# TEC_driver.net
KiCad netlist of a schematic drawn in Altium Designer
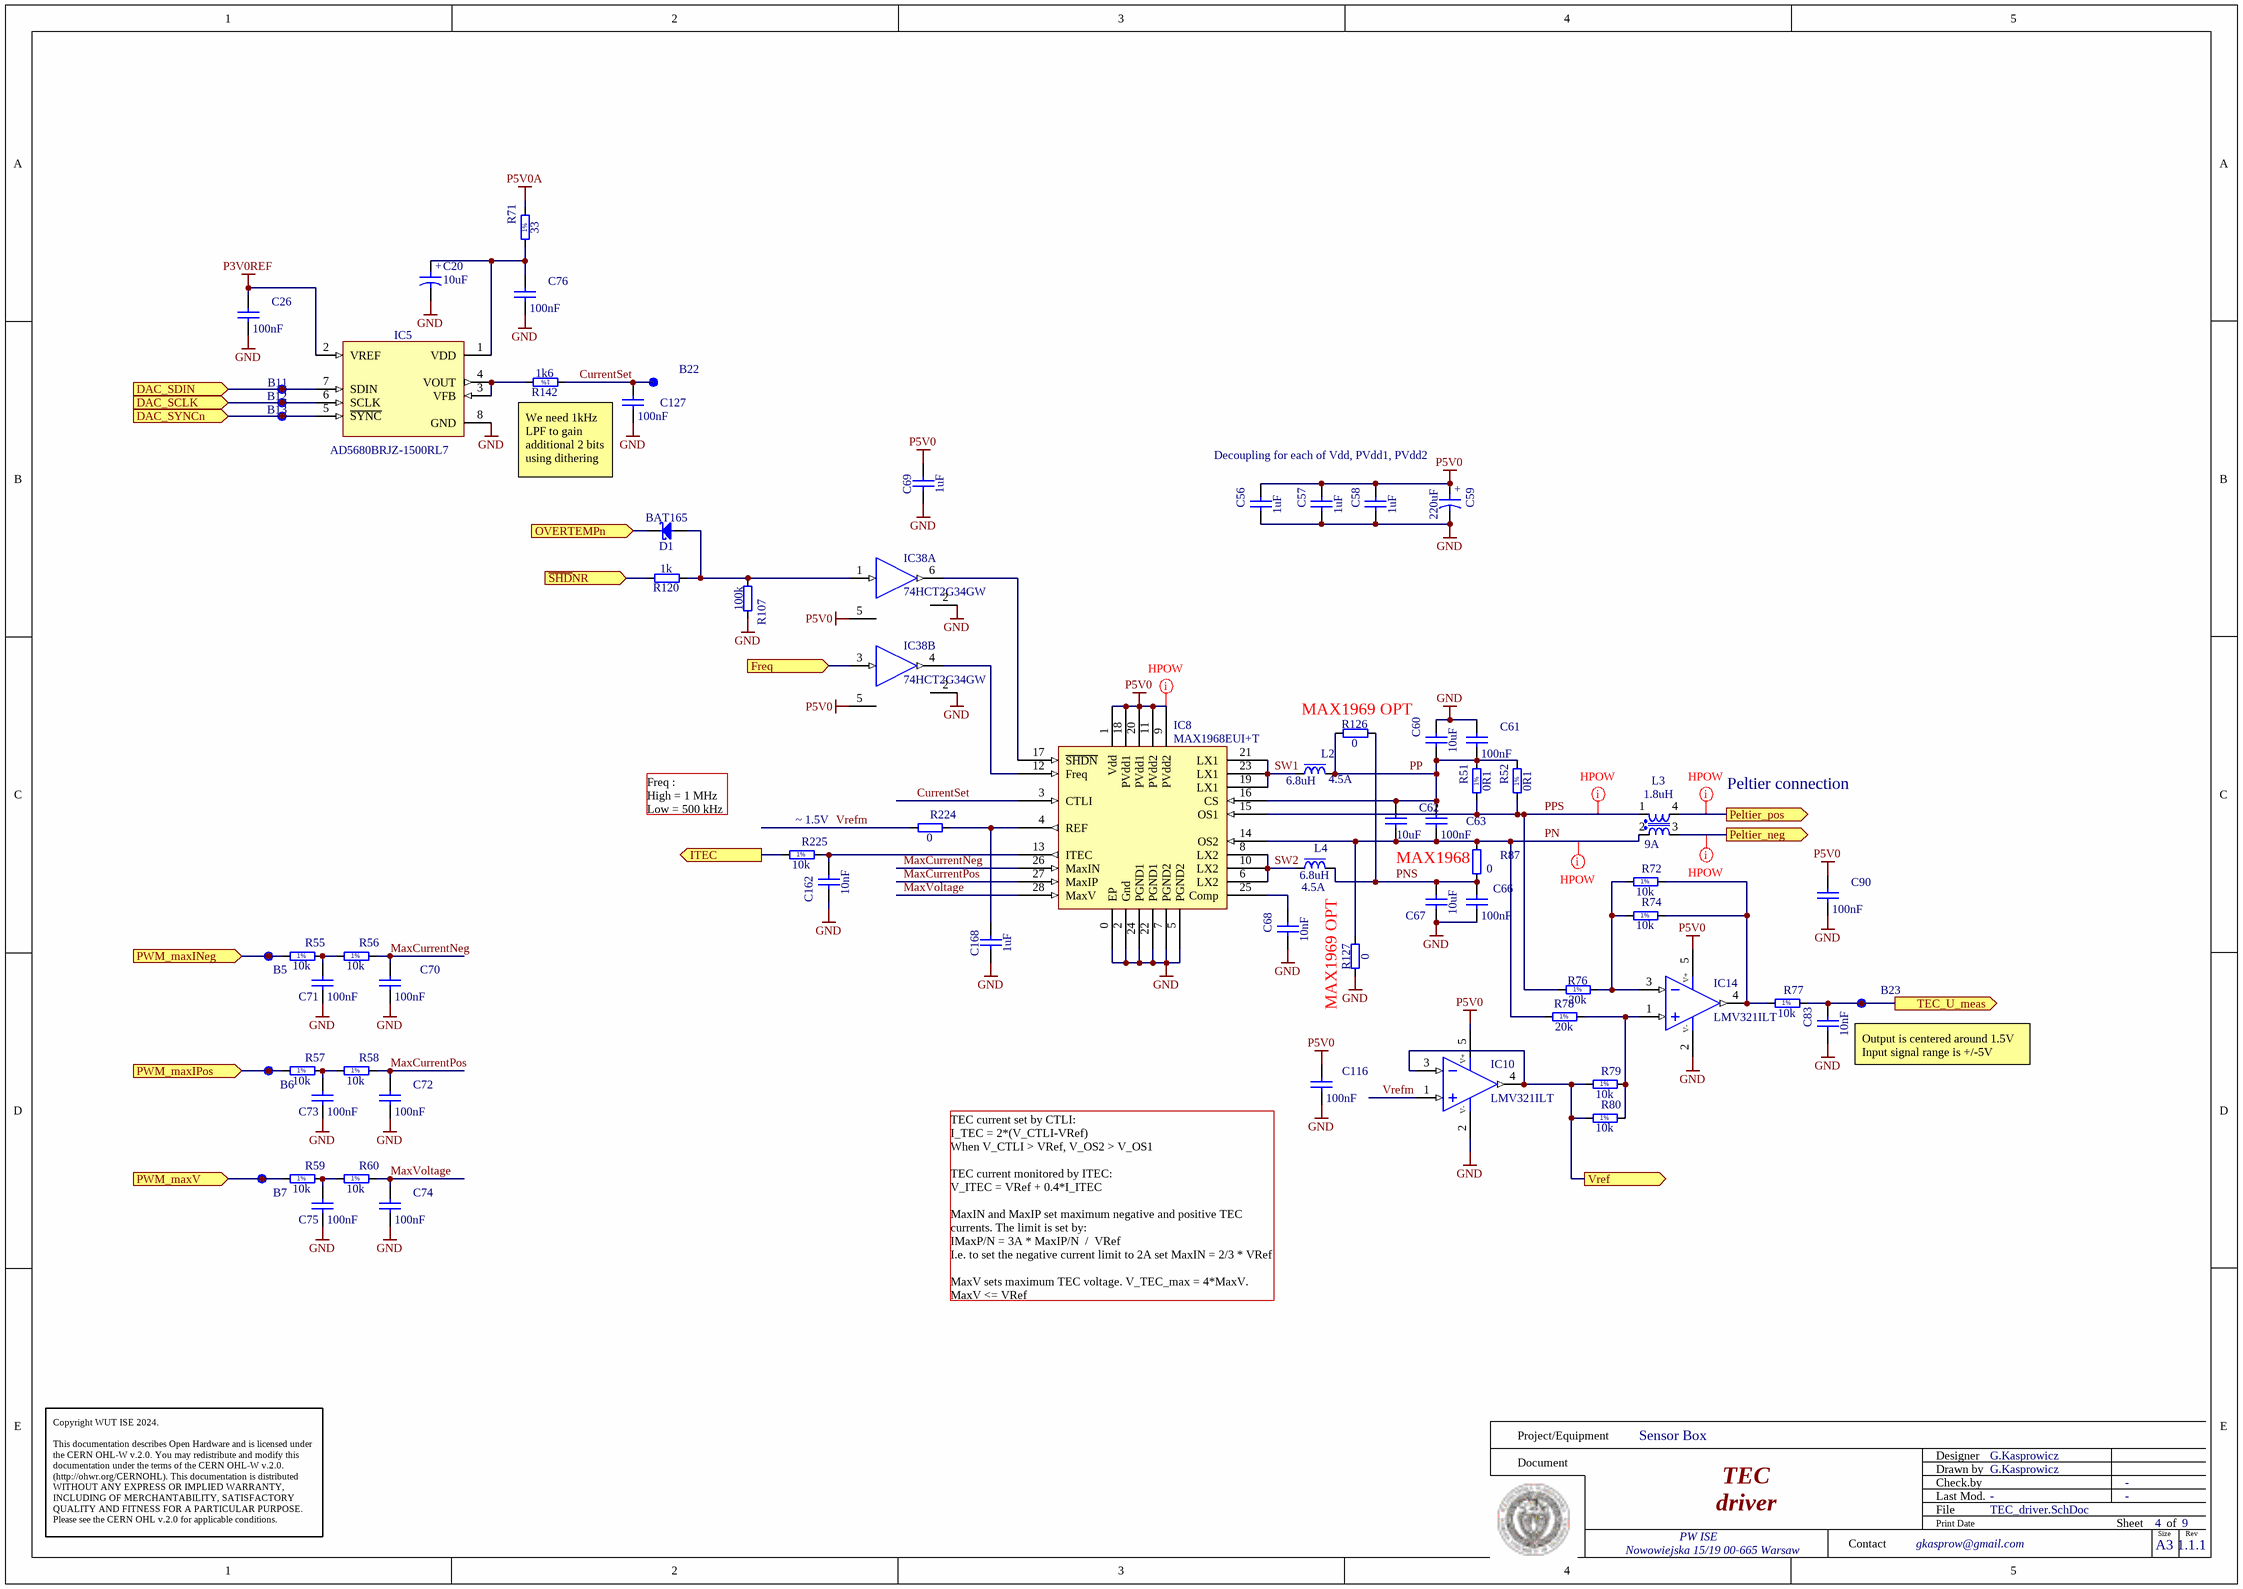
[diagram p0: TEC_driver.SchDoc]

(export (version "E")
  (design (tool "Eeschema 10.0.6"))
  (components
    (comp (ref "B5")
      (value "SMD Pad")
      (footprint "C100")
      (description "Through Hole Pad")
      (fields (field (name "PART NUMBER") "SMD_PAD_D1MM") (field (name "AUTHOR") "CERN DEM JLC"))
      (libsource (lib "Eletro-mechanical") (part "Single SMD Pad (Round)"))
    )
    (comp (ref "B6")
      (value "SMD Pad")
      (footprint "C100")
      (description "Through Hole Pad")
      (fields (field (name "PART NUMBER") "SMD_PAD_D1MM") (field (name "AUTHOR") "CERN DEM JLC"))
      (libsource (lib "Eletro-mechanical") (part "Single SMD Pad (Round)"))
    )
    (comp (ref "B7")
      (value "SMD Pad")
      (footprint "C100")
      (description "Through Hole Pad")
      (fields (field (name "PART NUMBER") "SMD_PAD_D1MM") (field (name "AUTHOR") "CERN DEM JLC"))
      (libsource (lib "Eletro-mechanical") (part "Single SMD Pad (Round)"))
    )
    (comp (ref "B11")
      (value "SMD Pad")
      (footprint "C100")
      (description "Through Hole Pad")
      (fields (field (name "PART NUMBER") "SMD_PAD_D1MM") (field (name "AUTHOR") "CERN DEM JLC"))
      (libsource (lib "Eletro-mechanical") (part "Single SMD Pad (Round)"))
    )
    (comp (ref "B12")
      (value "SMD Pad")
      (footprint "C100")
      (description "Through Hole Pad")
      (fields (field (name "PART NUMBER") "SMD_PAD_D1MM") (field (name "AUTHOR") "CERN DEM JLC"))
      (libsource (lib "Eletro-mechanical") (part "Single SMD Pad (Round)"))
    )
    (comp (ref "B13")
      (value "SMD Pad")
      (footprint "C100")
      (description "Through Hole Pad")
      (fields (field (name "PART NUMBER") "SMD_PAD_D1MM") (field (name "AUTHOR") "CERN DEM JLC"))
      (libsource (lib "Eletro-mechanical") (part "Single SMD Pad (Round)"))
    )
    (comp (ref "B22")
      (value "SMD Pad")
      (footprint "C100")
      (description "Through Hole Pad")
      (fields (field (name "PART NUMBER") "SMD_PAD_D1MM") (field (name "AUTHOR") "CERN DEM JLC"))
      (libsource (lib "Eletro-mechanical") (part "Single SMD Pad (Round)"))
    )
    (comp (ref "B23")
      (value "SMD Pad")
      (footprint "C100")
      (description "Through Hole Pad")
      (fields (field (name "PART NUMBER") "SMD_PAD_D1MM") (field (name "AUTHOR") "CERN DEM JLC"))
      (libsource (lib "Eletro-mechanical") (part "Single SMD Pad (Round)"))
    )
    (comp (ref "C20")
      (value "10uF")
      (footprint "CAPMP3216X180N")
      (description "Polarised capacitor")
      (fields
        (field (name "PART NUMBER") "CTE3216-18_10UF_16V_20%_AVX_TCJ")
        (field (name "VOLTAGE") "16V")
        (field (name "AUTHOR") "CERN DEM JLC")
      )
      (libsource (lib "Capacitors") (part "Capacitor - polarized"))
    )
    (comp (ref "C26")
      (value "100nF")
      (footprint "CAPC1005X55N")
      (description "Non-polarised capacitor")
      (fields
        (field (name "PART NUMBER") "CC0402_100NF_16V_10%_X5R")
        (field (name "VOLTAGE") "16V")
        (field (name "AUTHOR") "CERN DEM JLC")
      )
      (libsource (lib "Capacitors") (part "Capacitor - non polarized"))
    )
    (comp (ref "C56")
      (value "1uF")
      (footprint "CAPC1608X87N")
      (description "Non-polarised capacitor")
      (fields
        (field (name "PART NUMBER") "CC0603_1UF_25V_10%_X7R")
        (field (name "VOLTAGE") "25V")
        (field (name "AUTHOR") "CERN DEM JLC")
      )
      (libsource (lib "Capacitors") (part "Capacitor - non polarized"))
    )
    (comp (ref "C57")
      (value "1uF")
      (footprint "CAPC1608X87N")
      (description "Non-polarised capacitor")
      (fields
        (field (name "PART NUMBER") "CC0603_1UF_25V_10%_X7R")
        (field (name "VOLTAGE") "25V")
        (field (name "AUTHOR") "CERN DEM JLC")
      )
      (libsource (lib "Capacitors") (part "Capacitor - non polarized"))
    )
    (comp (ref "C58")
      (value "1uF")
      (footprint "CAPC1608X87N")
      (description "Non-polarised capacitor")
      (fields
        (field (name "PART NUMBER") "CC0603_1UF_25V_10%_X7R")
        (field (name "VOLTAGE") "25V")
        (field (name "AUTHOR") "CERN DEM JLC")
      )
      (libsource (lib "Capacitors") (part "Capacitor - non polarized"))
    )
    (comp (ref "C59")
      (value "220uF")
      (footprint "CAPMP7343X430N")
      (description "Polarised capacitor")
      (fields
        (field (name "PART NUMBER") "CTE7343-43_220UF_16V_10%")
        (field (name "VOLTAGE") "16V")
        (field (name "AUTHOR") "CERN DEM JLC")
      )
      (libsource (lib "Capacitors") (part "Capacitor - polarized"))
    )
    (comp (ref "C60")
      (value "10uF")
      (footprint "CAPC2012X135N")
      (description "Non-polarised capacitor")
      (fields
        (field (name "PART NUMBER") "CC0805_10UF_16V_10%_X5R")
        (field (name "VOLTAGE") "16V")
        (field (name "AUTHOR") "CERN DEM JLC")
      )
      (libsource (lib "Capacitors") (part "Capacitor - non polarized"))
    )
    (comp (ref "C61")
      (value "100nF")
      (footprint "CAPC1005X55N")
      (description "Non-polarised capacitor")
      (fields
        (field (name "PART NUMBER") "CC0402_100NF_16V_10%_X5R")
        (field (name "VOLTAGE") "16V")
        (field (name "AUTHOR") "CERN DEM JLC")
      )
      (libsource (lib "Capacitors") (part "Capacitor - non polarized"))
    )
    (comp (ref "C62")
      (value "10uF")
      (footprint "CAPC2012X135N")
      (description "Non-polarised capacitor")
      (fields
        (field (name "PART NUMBER") "CC0805_10UF_16V_10%_X5R")
        (field (name "VOLTAGE") "16V")
        (field (name "AUTHOR") "CERN DEM JLC")
      )
      (libsource (lib "Capacitors") (part "Capacitor - non polarized"))
    )
    (comp (ref "C63")
      (value "100nF")
      (footprint "CAPC1005X55N")
      (description "Non-polarised capacitor")
      (fields
        (field (name "PART NUMBER") "CC0402_100NF_16V_10%_X5R")
        (field (name "VOLTAGE") "16V")
        (field (name "AUTHOR") "CERN DEM JLC")
      )
      (libsource (lib "Capacitors") (part "Capacitor - non polarized"))
    )
    (comp (ref "C66")
      (value "100nF")
      (footprint "CAPC1005X55N")
      (description "Non-polarised capacitor")
      (fields
        (field (name "PART NUMBER") "CC0402_100NF_16V_10%_X5R")
        (field (name "VOLTAGE") "16V")
        (field (name "AUTHOR") "CERN DEM JLC")
      )
      (libsource (lib "Capacitors") (part "Capacitor - non polarized"))
    )
    (comp (ref "C67")
      (value "10uF")
      (footprint "CAPC2012X135N")
      (description "Non-polarised capacitor")
      (fields
        (field (name "PART NUMBER") "CC0805_10UF_16V_10%_X5R")
        (field (name "VOLTAGE") "16V")
        (field (name "AUTHOR") "CERN DEM JLC")
      )
      (libsource (lib "Capacitors") (part "Capacitor - non polarized"))
    )
    (comp (ref "C68")
      (value "10nF")
      (footprint "CAPC1005X55N")
      (description "Non-polarised capacitor")
      (fields
        (field (name "PART NUMBER") "CC0402_10NF_25V_10%_X7R")
        (field (name "VOLTAGE") "25V")
        (field (name "AUTHOR") "CERN DEM JLC")
      )
      (libsource (lib "Capacitors") (part "Capacitor - non polarized"))
    )
    (comp (ref "C69")
      (value "1uF")
      (footprint "CAPC1608X87N")
      (description "Non-polarised capacitor")
      (fields
        (field (name "PART NUMBER") "CC0603_1UF_25V_10%_X7R")
        (field (name "VOLTAGE") "25V")
        (field (name "AUTHOR") "CERN DEM JLC")
      )
      (libsource (lib "Capacitors") (part "Capacitor - non polarized"))
    )
    (comp (ref "C70")
      (value "100nF")
      (footprint "CAPC1005X55N")
      (description "Non-polarised capacitor")
      (fields
        (field (name "PART NUMBER") "CC0402_100NF_16V_10%_X5R")
        (field (name "VOLTAGE") "16V")
        (field (name "AUTHOR") "CERN DEM JLC")
      )
      (libsource (lib "Capacitors") (part "Capacitor - non polarized"))
    )
    (comp (ref "C71")
      (value "100nF")
      (footprint "CAPC1005X55N")
      (description "Non-polarised capacitor")
      (fields
        (field (name "PART NUMBER") "CC0402_100NF_16V_10%_X5R")
        (field (name "VOLTAGE") "16V")
        (field (name "AUTHOR") "CERN DEM JLC")
      )
      (libsource (lib "Capacitors") (part "Capacitor - non polarized"))
    )
    (comp (ref "C72")
      (value "100nF")
      (footprint "CAPC1005X55N")
      (description "Non-polarised capacitor")
      (fields
        (field (name "PART NUMBER") "CC0402_100NF_16V_10%_X5R")
        (field (name "VOLTAGE") "16V")
        (field (name "AUTHOR") "CERN DEM JLC")
      )
      (libsource (lib "Capacitors") (part "Capacitor - non polarized"))
    )
    (comp (ref "C73")
      (value "100nF")
      (footprint "CAPC1005X55N")
      (description "Non-polarised capacitor")
      (fields
        (field (name "PART NUMBER") "CC0402_100NF_16V_10%_X5R")
        (field (name "VOLTAGE") "16V")
        (field (name "AUTHOR") "CERN DEM JLC")
      )
      (libsource (lib "Capacitors") (part "Capacitor - non polarized"))
    )
    (comp (ref "C74")
      (value "100nF")
      (footprint "CAPC1005X55N")
      (description "Non-polarised capacitor")
      (fields
        (field (name "PART NUMBER") "CC0402_100NF_16V_10%_X5R")
        (field (name "VOLTAGE") "16V")
        (field (name "AUTHOR") "CERN DEM JLC")
      )
      (libsource (lib "Capacitors") (part "Capacitor - non polarized"))
    )
    (comp (ref "C75")
      (value "100nF")
      (footprint "CAPC1005X55N")
      (description "Non-polarised capacitor")
      (fields
        (field (name "PART NUMBER") "CC0402_100NF_16V_10%_X5R")
        (field (name "VOLTAGE") "16V")
        (field (name "AUTHOR") "CERN DEM JLC")
      )
      (libsource (lib "Capacitors") (part "Capacitor - non polarized"))
    )
    (comp (ref "C76")
      (value "100nF")
      (footprint "CAPC1005X55N")
      (description "Non-polarised capacitor")
      (fields
        (field (name "PART NUMBER") "CC0402_100NF_16V_10%_X5R")
        (field (name "VOLTAGE") "16V")
        (field (name "AUTHOR") "CERN DEM JLC")
      )
      (libsource (lib "Capacitors") (part "Capacitor - non polarized"))
    )
    (comp (ref "C83")
      (value "10nF")
      (footprint "CAPC1005X55N")
      (description "Non-polarised capacitor")
      (fields
        (field (name "PART NUMBER") "CC0402_10NF_25V_10%_X7R")
        (field (name "VOLTAGE") "25V")
        (field (name "AUTHOR") "CERN DEM JLC")
      )
      (libsource (lib "Capacitors") (part "Capacitor - non polarized"))
    )
    (comp (ref "C90")
      (value "100nF")
      (footprint "CAPC1005X55N")
      (description "Non-polarised capacitor")
      (fields
        (field (name "PART NUMBER") "CC0402_100NF_16V_10%_X5R")
        (field (name "VOLTAGE") "16V")
        (field (name "AUTHOR") "CERN DEM JLC")
      )
      (libsource (lib "Capacitors") (part "Capacitor - non polarized"))
    )
    (comp (ref "C116")
      (value "100nF")
      (footprint "CAPC1005X55N")
      (description "Non-polarised capacitor")
      (fields
        (field (name "PART NUMBER") "CC0402_100NF_16V_10%_X5R")
        (field (name "VOLTAGE") "16V")
        (field (name "AUTHOR") "CERN DEM JLC")
      )
      (libsource (lib "Capacitors") (part "Capacitor - non polarized"))
    )
    (comp (ref "C127")
      (value "100nF")
      (footprint "CAPC1005X55N")
      (description "Non-polarised capacitor")
      (fields
        (field (name "PART NUMBER") "CC0402_100NF_16V_10%_X5R")
        (field (name "VOLTAGE") "16V")
        (field (name "AUTHOR") "CERN DEM JLC")
      )
      (libsource (lib "Capacitors") (part "Capacitor - non polarized"))
    )
    (comp (ref "C162")
      (value "10nF")
      (footprint "CAPC1005X55N")
      (description "Non-polarised capacitor")
      (fields
        (field (name "PART NUMBER") "CC0402_10NF_25V_10%_X7R")
        (field (name "VOLTAGE") "25V")
        (field (name "AUTHOR") "CERN DEM JLC")
      )
      (libsource (lib "Capacitors") (part "Capacitor - non polarized"))
    )
    (comp (ref "C168")
      (value "1uF")
      (footprint "CAPC1608X87N")
      (description "Non-polarised capacitor")
      (fields
        (field (name "PART NUMBER") "CC0603_1UF_25V_10%_X7R")
        (field (name "VOLTAGE") "25V")
        (field (name "AUTHOR") "CERN DEM JLC")
      )
      (libsource (lib "Capacitors") (part "Capacitor - non polarized"))
    )
    (comp (ref "D1")
      (value "BAT165")
      (footprint "SOD2512X110N")
      (description "Schottky Diode")
      (fields
        (field (name "VOLTAGE") "40V")
        (field (name "POWER") "750mA")
        (field (name "AUTHOR") "CERN DEM JLC")
      )
      (libsource (lib "ICs And Semiconductors") (part "Diode Schottky"))
    )
    (comp (ref "IC5")
      (value "AD5680BRJZ-1500RL7")
      (footprint "SOT65P280X145-8N")
      (description "5V 18-Bit nanoDAC®in a SOT-23")
      (fields (field (name "MANUFACTURER") "ANALOG DEVICES") (field (name "AUTHOR") "GK"))
      (libsource (lib "LIBRARY_SCH") (part "DAC_AD5680BRJZ"))
    )
    (comp (ref "IC8")
      (value "MAX1968EUI+T")
      (footprint "TSSOP28-EP")
      (description "Power peltier driver. bipolar")
      (fields (field (name "PUBLISHER") "Altium Limited"))
      (libsource (lib "LIBRARY_SCH") (part "DRV_MAX1968"))
    )
    (comp (ref "IC10")
      (value "LMV321ILT")
      (footprint "SOT95P280X145-5N")
      (description "Operational Amplifier")
      (fields (field (name "MANUFACTURER") "ST MICROELECTRONICS") (field (name "AUTHOR") "CERN DEM MR"))
      (libsource (lib "ICs And Semiconductors") (part "Operational Amplifier Type10"))
    )
    (comp (ref "IC14")
      (value "LMV321ILT")
      (footprint "SOT95P280X145-5N")
      (description "Operational Amplifier")
      (fields (field (name "MANUFACTURER") "ST MICROELECTRONICS") (field (name "AUTHOR") "CERN DEM MR"))
      (libsource (lib "ICs And Semiconductors") (part "Operational Amplifier Type10"))
    )
    (comp (ref "IC38")
      (value "74HCT2G34GW")
      (footprint "SOT65P210X110-6N")
      (description "Dual Buffer Gate")
      (fields (field (name "MANUFACTURER") "TEXAS INSTRUMENTS") (field (name "AUTHOR") "GK"))
      (libsource (lib "ICS-logic") (part "74HCT2G34GW"))
    )
    (comp (ref "L2")
      (value "6.8uH")
      (footprint "INDM6965X300N")
      (description "Inductor With Core")
      (fields
        (field (name "PART NUMBER") "IND2525_6.8UH_20%_VISHAY_IHLP-2525CZ-01")
        (field (name "POWER") "4.5A")
        (field (name "TOLERANCE") "±20%")
        (field (name "AUTHOR") "CERN DEM MR")
      )
      (libsource (lib "Inductors & Transformers") (part "Inductor With Magnetic core"))
    )
    (comp (ref "L3")
      (value "1.8uH")
      (footprint "IND_PULSE_PA4339")
      (description "1.8uH 9A 10mR CMC")
      (fields
        (field (name "PART NUMBER") "PA4339.101NLT")
        (field (name "TOLERANCE") "±50%")
        (field (name "POWER") "9A")
        (field (name "AUTHOR") "GK")
      )
      (libsource (lib "Inductors_Transformers") (part "L_CMC_PA4339.101NLT"))
    )
    (comp (ref "L4")
      (value "6.8uH")
      (footprint "INDM6965X300N")
      (description "Inductor With Core")
      (fields
        (field (name "PART NUMBER") "IND2525_6.8UH_20%_VISHAY_IHLP-2525CZ-01")
        (field (name "POWER") "4.5A")
        (field (name "TOLERANCE") "±20%")
        (field (name "AUTHOR") "CERN DEM MR")
      )
      (libsource (lib "Inductors & Transformers") (part "Inductor With Magnetic core"))
    )
    (comp (ref "R51")
      (value "0R1")
      (footprint "RESC3216X65N")
      (description "Resistor - 1%")
      (fields
        (field (name "PART NUMBER") "R1206_0R1_1%_0.25W_100PPM_YAGEO_PT")
        (field (name "POWER") "0.25W")
        (field (name "AUTHOR") "CERN DEM JMW")
      )
      (libsource (lib "Resistors") (part "Resistor - 1%"))
    )
    (comp (ref "R52")
      (value "0R1")
      (footprint "RESC3216X65N")
      (description "Resistor - 1%")
      (fields
        (field (name "PART NUMBER") "R1206_0R1_1%_0.25W_100PPM_YAGEO_PT")
        (field (name "POWER") "0.25W")
        (field (name "AUTHOR") "CERN DEM JMW")
      )
      (libsource (lib "Resistors") (part "Resistor - 1%"))
    )
    (comp (ref "R55")
      (value "10k")
      (footprint "RESC1005X40N")
      (description "Resistor - 1%")
      (fields
        (field (name "PART NUMBER") "R0402_10K_1%_0.0625W_100PPM")
        (field (name "POWER") "0.0625W")
        (field (name "AUTHOR") "CERN DEM JLC")
      )
      (libsource (lib "Resistors") (part "Resistor - 1%"))
    )
    (comp (ref "R56")
      (value "10k")
      (footprint "RESC1005X40N")
      (description "Resistor - 1%")
      (fields
        (field (name "PART NUMBER") "R0402_10K_1%_0.0625W_100PPM")
        (field (name "POWER") "0.0625W")
        (field (name "AUTHOR") "CERN DEM JLC")
      )
      (libsource (lib "Resistors") (part "Resistor - 1%"))
    )
    (comp (ref "R57")
      (value "10k")
      (footprint "RESC1005X40N")
      (description "Resistor - 1%")
      (fields
        (field (name "PART NUMBER") "R0402_10K_1%_0.0625W_100PPM")
        (field (name "POWER") "0.0625W")
        (field (name "AUTHOR") "CERN DEM JLC")
      )
      (libsource (lib "Resistors") (part "Resistor - 1%"))
    )
    (comp (ref "R58")
      (value "10k")
      (footprint "RESC1005X40N")
      (description "Resistor - 1%")
      (fields
        (field (name "PART NUMBER") "R0402_10K_1%_0.0625W_100PPM")
        (field (name "POWER") "0.0625W")
        (field (name "AUTHOR") "CERN DEM JLC")
      )
      (libsource (lib "Resistors") (part "Resistor - 1%"))
    )
    (comp (ref "R59")
      (value "10k")
      (footprint "RESC1005X40N")
      (description "Resistor - 1%")
      (fields
        (field (name "PART NUMBER") "R0402_10K_1%_0.0625W_100PPM")
        (field (name "POWER") "0.0625W")
        (field (name "AUTHOR") "CERN DEM JLC")
      )
      (libsource (lib "Resistors") (part "Resistor - 1%"))
    )
    (comp (ref "R60")
      (value "10k")
      (footprint "RESC1005X40N")
      (description "Resistor - 1%")
      (fields
        (field (name "PART NUMBER") "R0402_10K_1%_0.0625W_100PPM")
        (field (name "POWER") "0.0625W")
        (field (name "AUTHOR") "CERN DEM JLC")
      )
      (libsource (lib "Resistors") (part "Resistor - 1%"))
    )
    (comp (ref "R71")
      (value "33")
      (footprint "RESC1005X40N")
      (description "Resistor - 1%")
      (fields
        (field (name "PART NUMBER") "R0402_33R_1%_0.0625W_100PPM")
        (field (name "POWER") "0.0625W")
        (field (name "AUTHOR") "CERN DEM JLC")
      )
      (libsource (lib "Resistors") (part "Resistor - 1%"))
    )
    (comp (ref "R72")
      (value "10k")
      (footprint "RESC1005X40N")
      (description "Resistor - 1%")
      (fields
        (field (name "PART NUMBER") "R0402_10K_1%_0.0625W_100PPM")
        (field (name "POWER") "0.0625W")
        (field (name "AUTHOR") "CERN DEM JLC")
      )
      (libsource (lib "Resistors") (part "Resistor - 1%"))
    )
    (comp (ref "R74")
      (value "10k")
      (footprint "RESC1005X40N")
      (description "Resistor - 1%")
      (fields
        (field (name "PART NUMBER") "R0402_10K_1%_0.0625W_100PPM")
        (field (name "POWER") "0.0625W")
        (field (name "AUTHOR") "CERN DEM JLC")
      )
      (libsource (lib "Resistors") (part "Resistor - 1%"))
    )
    (comp (ref "R76")
      (value "20k")
      (footprint "RESC1005X40N")
      (description "Resistor - 1%")
      (fields
        (field (name "PART NUMBER") "R0402_20K_1%_0.0625W_100PPM")
        (field (name "POWER") "0.0625W")
        (field (name "AUTHOR") "CERN DEM JLC")
      )
      (libsource (lib "Resistors") (part "Resistor - 1%"))
    )
    (comp (ref "R77")
      (value "10k")
      (footprint "RESC1005X40N")
      (description "Resistor - 1%")
      (fields
        (field (name "PART NUMBER") "R0402_10K_1%_0.0625W_100PPM")
        (field (name "POWER") "0.0625W")
        (field (name "AUTHOR") "CERN DEM JLC")
      )
      (libsource (lib "Resistors") (part "Resistor - 1%"))
    )
    (comp (ref "R78")
      (value "20k")
      (footprint "RESC1005X40N")
      (description "Resistor - 1%")
      (fields
        (field (name "PART NUMBER") "R0402_20K_1%_0.0625W_100PPM")
        (field (name "POWER") "0.0625W")
        (field (name "AUTHOR") "CERN DEM JLC")
      )
      (libsource (lib "Resistors") (part "Resistor - 1%"))
    )
    (comp (ref "R79")
      (value "10k")
      (footprint "RESC1005X40N")
      (description "Resistor - 1%")
      (fields
        (field (name "PART NUMBER") "R0402_10K_1%_0.0625W_100PPM")
        (field (name "POWER") "0.0625W")
        (field (name "AUTHOR") "CERN DEM JLC")
      )
      (libsource (lib "Resistors") (part "Resistor - 1%"))
    )
    (comp (ref "R80")
      (value "10k")
      (footprint "RESC1005X40N")
      (description "Resistor - 1%")
      (fields
        (field (name "PART NUMBER") "R0402_10K_1%_0.0625W_100PPM")
        (field (name "POWER") "0.0625W")
        (field (name "AUTHOR") "CERN DEM JLC")
      )
      (libsource (lib "Resistors") (part "Resistor - 1%"))
    )
    (comp (ref "R87")
      (value "0")
      (footprint "RESC3116X80N")
      (description "Resistor")
      (fields
        (field (name "PART NUMBER") "R1206_0R_JUMPER_SEI_HCJ")
        (field (name "MANUFACTURER") "SEI (STACKPOLE ELECTRONICS INC.)")
        (field (name "AUTHOR") "CERN DEM MR")
      )
      (libsource (lib "Resistors") (part "Resistor"))
    )
    (comp (ref "R107")
      (value "100k")
      (footprint "RESC1005X40N")
      (description "Resistor - 1%")
      (fields
        (field (name "PART NUMBER") "R0402_100K_1%_0.0625W_100PPM")
        (field (name "POWER") "0.0625W")
        (field (name "AUTHOR") "CERN DEM JLC")
      )
      (libsource (lib "Resistors") (part "Resistor - 1%"))
    )
    (comp (ref "R120")
      (value "1k")
      (footprint "RESC1005X40N")
      (description "Resistor - 1%")
      (fields
        (field (name "PART NUMBER") "R0402_1K_1%_0.0625W_100PPM")
        (field (name "POWER") "0.0625W")
        (field (name "AUTHOR") "CERN DEM JLC")
      )
      (libsource (lib "Resistors") (part "Resistor - 1%"))
    )
    (comp (ref "R126")
      (value "0")
      (footprint "RESC3116X80N")
      (description "Resistor")
      (fields
        (field (name "PART NUMBER") "R1206_0R_JUMPER_SEI_HCJ")
        (field (name "MANUFACTURER") "SEI (STACKPOLE ELECTRONICS INC.)")
        (field (name "AUTHOR") "CERN DEM MR")
      )
      (libsource (lib "Resistors") (part "Resistor"))
    )
    (comp (ref "R127")
      (value "0")
      (footprint "RESC3116X80N")
      (description "Resistor")
      (fields
        (field (name "PART NUMBER") "R1206_0R_JUMPER_SEI_HCJ")
        (field (name "MANUFACTURER") "SEI (STACKPOLE ELECTRONICS INC.)")
        (field (name "AUTHOR") "CERN DEM MR")
      )
      (libsource (lib "Resistors") (part "Resistor"))
    )
    (comp (ref "R142")
      (value "1k6")
      (footprint "RESC1005X40N")
      (description "Resistor - 1%")
      (fields
        (field (name "PART NUMBER") "R0402_1K6_1%_0.0625W_100PPM")
        (field (name "POWER") "0.0625W")
        (field (name "AUTHOR") "CERN DEM JLC")
      )
      (libsource (lib "Resistors") (part "Resistor - 1%"))
    )
    (comp (ref "R224")
      (value "0")
      (footprint "RESC1005X40N")
      (description "Resistor")
      (fields
        (field (name "PART NUMBER") "R0402_0R_JUMPER")
        (field (name "MANUFACTURER") "GENERIC")
        (field (name "AUTHOR") "CERN DEM JLC")
      )
      (libsource (lib "Resistors") (part "Resistor"))
    )
    (comp (ref "R225")
      (value "10k")
      (footprint "RESC1005X40N")
      (description "Resistor - 1%")
      (fields
        (field (name "PART NUMBER") "R0402_10K_1%_0.0625W_100PPM")
        (field (name "POWER") "0.0625W")
        (field (name "AUTHOR") "CERN DEM JLC")
      )
      (libsource (lib "Resistors") (part "Resistor - 1%"))
    )
  )
  (nets
    (net (code "1") (name "/CurrentSet") (class "Default")
      (node (ref "B22") (pin "1") (pinfunction "1_1") (pintype "bidirectional"))
      (node (ref "C127") (pin "1") (pinfunction "1_1") (pintype "passive"))
      (node (ref "IC8") (pin "3") (pinfunction "CTLI_3") (pintype "input"))
      (node (ref "R142") (pin "1") (pinfunction "1_1") (pintype "passive"))
    )
    (net (code "2") (name "/DAC_SCLK") (class "Default")
      (node (ref "B12") (pin "1") (pinfunction "1_1") (pintype "bidirectional"))
      (node (ref "IC5") (pin "6") (pinfunction "SCLK_6") (pintype "input"))
    )
    (net (code "3") (name "/DAC_SDIN") (class "Default")
      (node (ref "B11") (pin "1") (pinfunction "1_1") (pintype "bidirectional"))
      (node (ref "IC5") (pin "7") (pinfunction "SDIN_7") (pintype "input"))
    )
    (net (code "4") (name "/DAC_SYNCn") (class "Default")
      (node (ref "B13") (pin "1") (pinfunction "1_1") (pintype "bidirectional"))
      (node (ref "IC5") (pin "5") (pinfunction "~{SYNC}_5") (pintype "input"))
    )
    (net (code "5") (name "/Freq") (class "Default")
      (node (ref "IC38") (pin "3") (pinfunction "2A_3") (pintype "input"))
    )
    (net (code "6") (name "/ITEC") (class "Default")
      (node (ref "R225") (pin "1") (pinfunction "1_1") (pintype "passive"))
    )
    (net (code "7") (name "/MaxCurrentNeg") (class "Default")
      (node (ref "C70") (pin "1") (pinfunction "1_1") (pintype "passive"))
      (node (ref "IC8") (pin "26") (pinfunction "MaxIN_26") (pintype "input"))
      (node (ref "R56") (pin "2") (pinfunction "2_2") (pintype "passive"))
    )
    (net (code "8") (name "/MaxCurrentPos") (class "Default")
      (node (ref "C72") (pin "1") (pinfunction "1_1") (pintype "passive"))
      (node (ref "IC8") (pin "27") (pinfunction "MaxIP_27") (pintype "input"))
      (node (ref "R58") (pin "2") (pinfunction "2_2") (pintype "passive"))
    )
    (net (code "9") (name "/MaxVoltage") (class "Default")
      (node (ref "C74") (pin "1") (pinfunction "1_1") (pintype "passive"))
      (node (ref "IC8") (pin "28") (pinfunction "MaxV_28") (pintype "input"))
      (node (ref "R60") (pin "2") (pinfunction "2_2") (pintype "passive"))
    )
    (net (code "10") (name "/OVERTEMPn") (class "Default")
      (node (ref "D1") (pin "1") (pinfunction "C_1") (pintype "passive"))
    )
    (net (code "11") (name "/PN") (class "Default")
      (node (ref "C62") (pin "1") (pinfunction "1_1") (pintype "passive"))
      (node (ref "C63") (pin "2") (pinfunction "2_2") (pintype "passive"))
      (node (ref "IC8") (pin "14") (pinfunction "OS2_14") (pintype "input"))
      (node (ref "L3") (pin "2") (pinfunction "2_2") (pintype "passive"))
      (node (ref "R127") (pin "2") (pinfunction "2_2") (pintype "passive"))
      (node (ref "R78") (pin "1") (pinfunction "1_1") (pintype "passive"))
      (node (ref "R87") (pin "2") (pinfunction "2_2") (pintype "passive"))
    )
    (net (code "12") (name "/PNS") (class "Default")
      (node (ref "C66") (pin "1") (pinfunction "1_1") (pintype "passive"))
      (node (ref "C67") (pin "2") (pinfunction "2_2") (pintype "passive"))
      (node (ref "L4") (pin "2") (pinfunction "2_2") (pintype "passive"))
      (node (ref "R126") (pin "2") (pinfunction "2_2") (pintype "passive"))
      (node (ref "R87") (pin "1") (pinfunction "1_1") (pintype "passive"))
    )
    (net (code "13") (name "/PP") (class "Default")
      (node (ref "C60") (pin "1") (pinfunction "1_1") (pintype "passive"))
      (node (ref "C61") (pin "2") (pinfunction "2_2") (pintype "passive"))
      (node (ref "C62") (pin "2") (pinfunction "2_2") (pintype "passive"))
      (node (ref "C63") (pin "1") (pinfunction "1_1") (pintype "passive"))
      (node (ref "IC8") (pin "16") (pinfunction "CS_16") (pintype "input"))
      (node (ref "L2") (pin "2") (pinfunction "2_2") (pintype "passive"))
      (node (ref "R126") (pin "1") (pinfunction "1_1") (pintype "passive"))
      (node (ref "R51") (pin "2") (pinfunction "2_2") (pintype "passive"))
      (node (ref "R52") (pin "2") (pinfunction "2_2") (pintype "passive"))
    )
    (net (code "14") (name "/PPS") (class "Default")
      (node (ref "IC8") (pin "15") (pinfunction "OS1_15") (pintype "input"))
      (node (ref "L3") (pin "1") (pinfunction "1_1") (pintype "passive"))
      (node (ref "R51") (pin "1") (pinfunction "1_1") (pintype "passive"))
      (node (ref "R52") (pin "1") (pinfunction "1_1") (pintype "passive"))
      (node (ref "R76") (pin "1") (pinfunction "1_1") (pintype "passive"))
    )
    (net (code "15") (name "/PWM_maxINeg") (class "Default")
      (node (ref "B5") (pin "1") (pinfunction "1_1") (pintype "bidirectional"))
      (node (ref "R55") (pin "1") (pinfunction "1_1") (pintype "passive"))
    )
    (net (code "16") (name "/PWM_maxIPos") (class "Default")
      (node (ref "B6") (pin "1") (pinfunction "1_1") (pintype "bidirectional"))
      (node (ref "R57") (pin "1") (pinfunction "1_1") (pintype "passive"))
    )
    (net (code "17") (name "/PWM_maxV") (class "Default")
      (node (ref "B7") (pin "1") (pinfunction "1_1") (pintype "bidirectional"))
      (node (ref "R59") (pin "1") (pinfunction "1_1") (pintype "passive"))
    )
    (net (code "18") (name "/Peltier_neg") (class "Default")
      (node (ref "L3") (pin "3") (pinfunction "3_3") (pintype "passive"))
    )
    (net (code "19") (name "/Peltier_pos") (class "Default")
      (node (ref "L3") (pin "4") (pinfunction "4_4") (pintype "passive"))
    )
    (net (code "20") (name "/SW1") (class "Default")
      (node (ref "IC8") (pin "19") (pinfunction "LX1_19") (pintype "power_in"))
      (node (ref "IC8") (pin "21") (pinfunction "LX1_21") (pintype "power_in"))
      (node (ref "IC8") (pin "23") (pinfunction "LX1_23") (pintype "power_in"))
      (node (ref "L2") (pin "1") (pinfunction "1_1") (pintype "passive"))
    )
    (net (code "21") (name "/SW2") (class "Default")
      (node (ref "IC8") (pin "10") (pinfunction "LX2_10") (pintype "power_in"))
      (node (ref "IC8") (pin "6") (pinfunction "LX2_6") (pintype "power_in"))
      (node (ref "IC8") (pin "8") (pinfunction "LX2_8") (pintype "power_in"))
      (node (ref "L4") (pin "1") (pinfunction "1_1") (pintype "passive"))
    )
    (net (code "22") (name "/TEC_U_meas") (class "Default")
      (node (ref "B23") (pin "1") (pinfunction "1_1") (pintype "bidirectional"))
      (node (ref "C83") (pin "2") (pinfunction "2_2") (pintype "passive"))
      (node (ref "R77") (pin "2") (pinfunction "2_2") (pintype "passive"))
    )
    (net (code "23") (name "/Vref") (class "Default")
      (node (ref "IC10") (pin "3") (pinfunction "IN-_3") (pintype "input"))
      (node (ref "IC10") (pin "4") (pinfunction "OUT_4") (pintype "output"))
      (node (ref "R79") (pin "1") (pinfunction "1_1") (pintype "passive"))
      (node (ref "R80") (pin "1") (pinfunction "1_1") (pintype "passive"))
    )
    (net (code "24") (name "/Vrefm") (class "Default")
      (node (ref "IC10") (pin "1") (pinfunction "IN+_1") (pintype "input"))
      (node (ref "R224") (pin "1") (pinfunction "1_1") (pintype "passive"))
    )
    (net (code "25") (name "/~{SHD}NR") (class "Default")
      (node (ref "R120") (pin "2") (pinfunction "2_2") (pintype "passive"))
    )
    (net (code "26") (name "GND") (class "Default")
      (node (ref "C116") (pin "2") (pinfunction "2_2") (pintype "passive"))
      (node (ref "C127") (pin "2") (pinfunction "2_2") (pintype "passive"))
      (node (ref "C162") (pin "1") (pinfunction "1_1") (pintype "passive"))
      (node (ref "C168") (pin "1") (pinfunction "1_1") (pintype "passive"))
      (node (ref "C20") (pin "2") (pinfunction "2_2") (pintype "passive"))
      (node (ref "C26") (pin "2") (pinfunction "2_2") (pintype "passive"))
      (node (ref "C56") (pin "1") (pinfunction "1_1") (pintype "passive"))
      (node (ref "C57") (pin "1") (pinfunction "1_1") (pintype "passive"))
      (node (ref "C58") (pin "1") (pinfunction "1_1") (pintype "passive"))
      (node (ref "C59") (pin "2") (pinfunction "2_2") (pintype "passive"))
      (node (ref "C60") (pin "2") (pinfunction "2_2") (pintype "passive"))
      (node (ref "C61") (pin "1") (pinfunction "1_1") (pintype "passive"))
      (node (ref "C66") (pin "2") (pinfunction "2_2") (pintype "passive"))
      (node (ref "C67") (pin "1") (pinfunction "1_1") (pintype "passive"))
      (node (ref "C68") (pin "1") (pinfunction "1_1") (pintype "passive"))
      (node (ref "C69") (pin "1") (pinfunction "1_1") (pintype "passive"))
      (node (ref "C70") (pin "2") (pinfunction "2_2") (pintype "passive"))
      (node (ref "C71") (pin "2") (pinfunction "2_2") (pintype "passive"))
      (node (ref "C72") (pin "2") (pinfunction "2_2") (pintype "passive"))
      (node (ref "C73") (pin "2") (pinfunction "2_2") (pintype "passive"))
      (node (ref "C74") (pin "2") (pinfunction "2_2") (pintype "passive"))
      (node (ref "C75") (pin "2") (pinfunction "2_2") (pintype "passive"))
      (node (ref "C76") (pin "2") (pinfunction "2_2") (pintype "passive"))
      (node (ref "C83") (pin "1") (pinfunction "1_1") (pintype "passive"))
      (node (ref "C90") (pin "2") (pinfunction "2_2") (pintype "passive"))
      (node (ref "IC10") (pin "2") (pinfunction "V-_2") (pintype "power_in"))
      (node (ref "IC14") (pin "2") (pinfunction "V-_2") (pintype "power_in"))
      (node (ref "IC38") (pin "2") (pinfunction "GND_2") (pintype "power_in"))
      (node (ref "IC5") (pin "8") (pinfunction "GND_8") (pintype "power_in"))
      (node (ref "IC8") (pin "0") (pinfunction "EP_0") (pintype "passive"))
      (node (ref "IC8") (pin "2") (pinfunction "Gnd_2") (pintype "power_in"))
      (node (ref "IC8") (pin "22") (pinfunction "PGND1_22") (pintype "power_in"))
      (node (ref "IC8") (pin "24") (pinfunction "PGND1_24") (pintype "power_in"))
      (node (ref "IC8") (pin "5") (pinfunction "PGND2_5") (pintype "power_in"))
      (node (ref "IC8") (pin "7") (pinfunction "PGND2_7") (pintype "power_in"))
      (node (ref "R107") (pin "2") (pinfunction "2_2") (pintype "passive"))
      (node (ref "R127") (pin "1") (pinfunction "1_1") (pintype "passive"))
    )
    (net (code "27") (name "Net-(C71-Pad1)") (class "Default")
      (node (ref "C71") (pin "1") (pinfunction "1_1") (pintype "passive"))
      (node (ref "R55") (pin "2") (pinfunction "2_2") (pintype "passive"))
      (node (ref "R56") (pin "1") (pinfunction "1_1") (pintype "passive"))
    )
    (net (code "28") (name "Net-(C73-Pad1)") (class "Default")
      (node (ref "C73") (pin "1") (pinfunction "1_1") (pintype "passive"))
      (node (ref "R57") (pin "2") (pinfunction "2_2") (pintype "passive"))
      (node (ref "R58") (pin "1") (pinfunction "1_1") (pintype "passive"))
    )
    (net (code "29") (name "Net-(C75-Pad1)") (class "Default")
      (node (ref "C75") (pin "1") (pinfunction "1_1") (pintype "passive"))
      (node (ref "R59") (pin "2") (pinfunction "2_2") (pintype "passive"))
      (node (ref "R60") (pin "1") (pinfunction "1_1") (pintype "passive"))
    )
    (net (code "30") (name "Net-(D1-A)") (class "Default")
      (node (ref "D1") (pin "2") (pinfunction "A_2") (pintype "passive"))
      (node (ref "IC38") (pin "1") (pinfunction "1A_1") (pintype "input"))
      (node (ref "R107") (pin "1") (pinfunction "1_1") (pintype "passive"))
      (node (ref "R120") (pin "1") (pinfunction "1_1") (pintype "passive"))
    )
    (net (code "31") (name "Net-(IC5-VDD)") (class "Default")
      (node (ref "C20") (pin "1") (pinfunction "1_1") (pintype "passive"))
      (node (ref "C76") (pin "1") (pinfunction "1_1") (pintype "passive"))
      (node (ref "IC5") (pin "1") (pinfunction "VDD_1") (pintype "power_in"))
      (node (ref "R71") (pin "1") (pinfunction "1_1") (pintype "passive"))
    )
    (net (code "32") (name "Net-(IC5-VFB)") (class "Default")
      (node (ref "IC5") (pin "3") (pinfunction "VFB_3") (pintype "input"))
      (node (ref "IC5") (pin "4") (pinfunction "VOUT_4") (pintype "output"))
      (node (ref "R142") (pin "2") (pinfunction "2_2") (pintype "passive"))
    )
    (net (code "33") (name "Net-(IC8-Comp)") (class "Default")
      (node (ref "C68") (pin "2") (pinfunction "2_2") (pintype "passive"))
      (node (ref "IC8") (pin "25") (pinfunction "Comp_25") (pintype "passive"))
    )
    (net (code "34") (name "Net-(IC8-ITEC)") (class "Default")
      (node (ref "C162") (pin "2") (pinfunction "2_2") (pintype "passive"))
      (node (ref "IC8") (pin "13") (pinfunction "ITEC_13") (pintype "output"))
      (node (ref "R225") (pin "2") (pinfunction "2_2") (pintype "passive"))
    )
    (net (code "35") (name "Net-(IC8-REF)") (class "Default")
      (node (ref "C168") (pin "2") (pinfunction "2_2") (pintype "passive"))
      (node (ref "IC8") (pin "4") (pinfunction "REF_4") (pintype "output"))
      (node (ref "R224") (pin "2") (pinfunction "2_2") (pintype "passive"))
    )
    (net (code "36") (name "Net-(IC14-IN+)") (class "Default")
      (node (ref "IC14") (pin "1") (pinfunction "IN+_1") (pintype "input"))
      (node (ref "R78") (pin "2") (pinfunction "2_2") (pintype "passive"))
      (node (ref "R79") (pin "2") (pinfunction "2_2") (pintype "passive"))
      (node (ref "R80") (pin "2") (pinfunction "2_2") (pintype "passive"))
    )
    (net (code "37") (name "Net-(IC14-IN-)") (class "Default")
      (node (ref "IC14") (pin "3") (pinfunction "IN-_3") (pintype "input"))
      (node (ref "R72") (pin "1") (pinfunction "1_1") (pintype "passive"))
      (node (ref "R74") (pin "1") (pinfunction "1_1") (pintype "passive"))
      (node (ref "R76") (pin "2") (pinfunction "2_2") (pintype "passive"))
    )
    (net (code "38") (name "Net-(IC14-OUT)") (class "Default")
      (node (ref "IC14") (pin "4") (pinfunction "OUT_4") (pintype "output"))
      (node (ref "R72") (pin "2") (pinfunction "2_2") (pintype "passive"))
      (node (ref "R74") (pin "2") (pinfunction "2_2") (pintype "passive"))
      (node (ref "R77") (pin "1") (pinfunction "1_1") (pintype "passive"))
    )
    (net (code "39") (name "Net-(IC38A-1Y)") (class "Default")
      (node (ref "IC38") (pin "6") (pinfunction "1Y_6") (pintype "output"))
      (node (ref "IC8") (pin "17") (pinfunction "~{SHDN}_17") (pintype "input"))
    )
    (net (code "40") (name "Net-(IC38B-2Y)") (class "Default")
      (node (ref "IC38") (pin "4") (pinfunction "2Y_4") (pintype "output"))
      (node (ref "IC8") (pin "12") (pinfunction "Freq_12") (pintype "input"))
    )
    (net (code "41") (name "P3V0REF") (class "Default")
      (node (ref "C26") (pin "1") (pinfunction "1_1") (pintype "passive"))
      (node (ref "IC5") (pin "2") (pinfunction "VREF_2") (pintype "input"))
    )
    (net (code "42") (name "P5V0") (class "Default")
      (node (ref "C116") (pin "1") (pinfunction "1_1") (pintype "passive"))
      (node (ref "C56") (pin "2") (pinfunction "2_2") (pintype "passive"))
      (node (ref "C57") (pin "2") (pinfunction "2_2") (pintype "passive"))
      (node (ref "C58") (pin "2") (pinfunction "2_2") (pintype "passive"))
      (node (ref "C59") (pin "1") (pinfunction "1_1") (pintype "passive"))
      (node (ref "C69") (pin "2") (pinfunction "2_2") (pintype "passive"))
      (node (ref "C90") (pin "1") (pinfunction "1_1") (pintype "passive"))
      (node (ref "IC10") (pin "5") (pinfunction "V+_5") (pintype "power_in"))
      (node (ref "IC14") (pin "5") (pinfunction "V+_5") (pintype "power_in"))
      (node (ref "IC38") (pin "5") (pinfunction "VCC_5") (pintype "power_in"))
      (node (ref "IC8") (pin "1") (pinfunction "Vdd_1") (pintype "power_in"))
      (node (ref "IC8") (pin "11") (pinfunction "PVdd2_11") (pintype "power_in"))
      (node (ref "IC8") (pin "18") (pinfunction "PVdd1_18") (pintype "power_in"))
      (node (ref "IC8") (pin "20") (pinfunction "PVdd1_20") (pintype "power_in"))
      (node (ref "IC8") (pin "9") (pinfunction "PVdd2_9") (pintype "power_in"))
    )
    (net (code "43") (name "P5V0A") (class "Default")
      (node (ref "R71") (pin "2") (pinfunction "2_2") (pintype "passive"))
    )
  )
)
